# POWER.net
KiCad netlist of a schematic drawn in Altium Designer
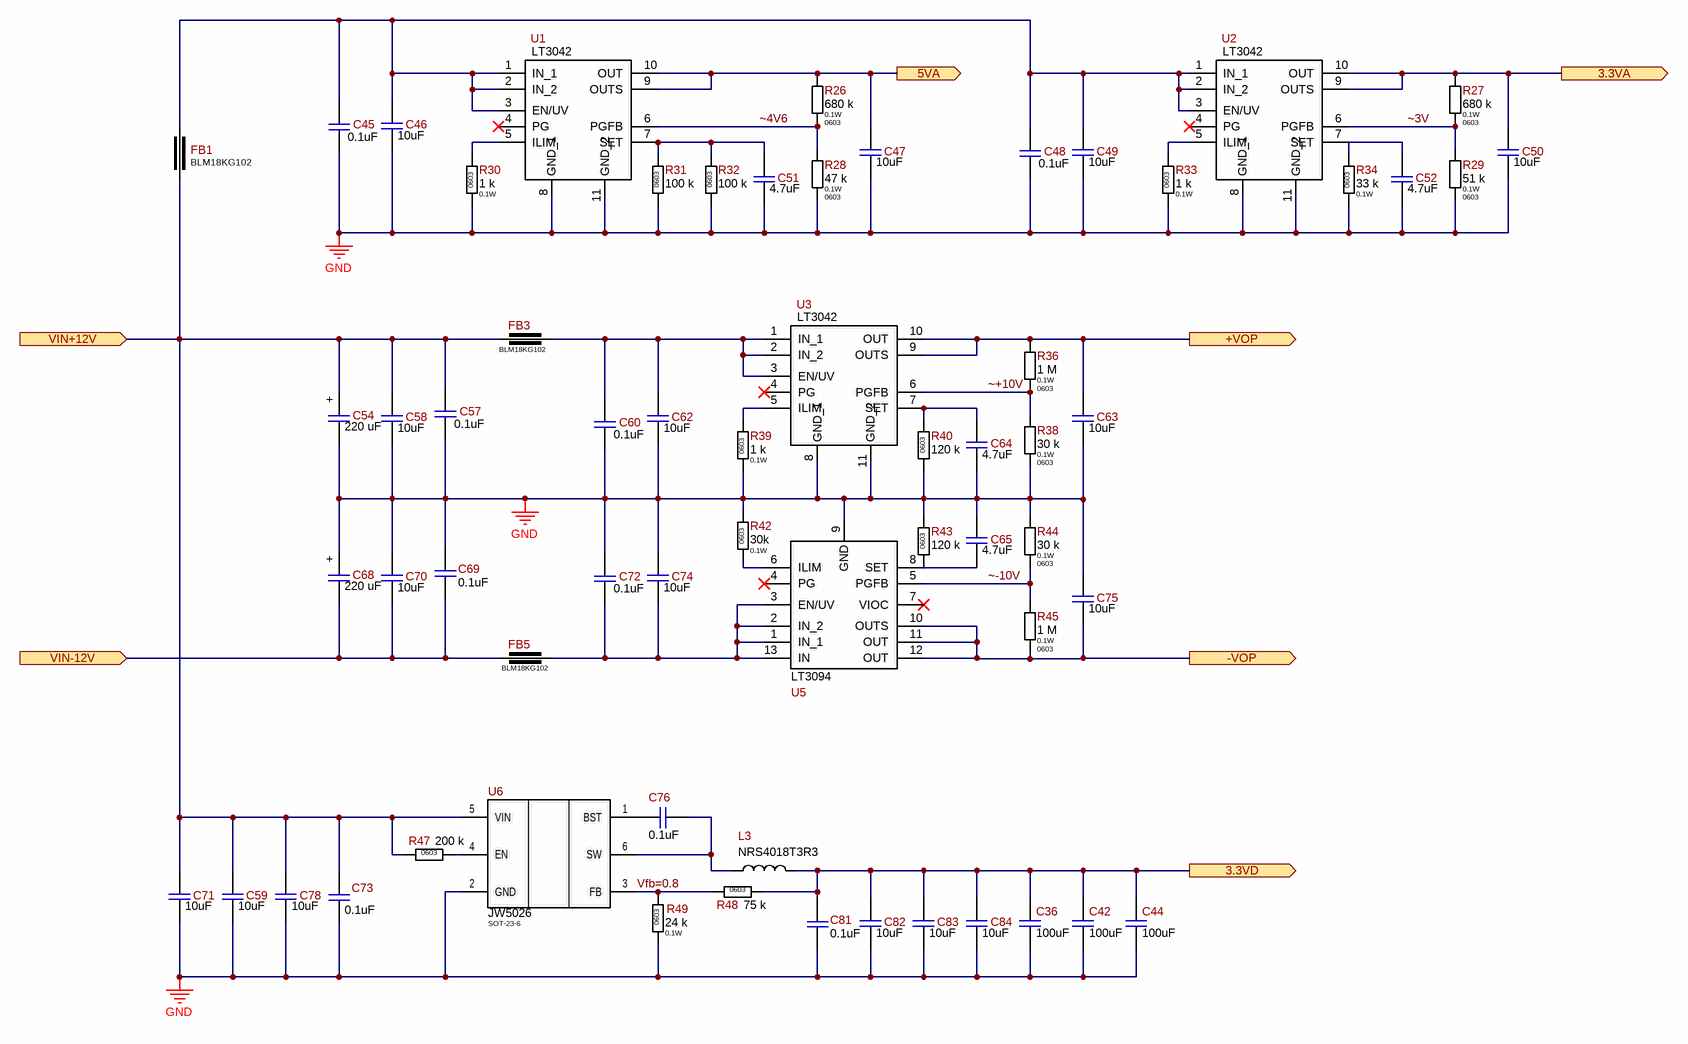
[diagram p0: POWER.SchDoc]

(export (version "E")
  (design (tool "Eeschema 10.0.6"))
  (components
    (comp (ref "C36")
      (value "100uF")
      (footprint "C1206(3216)")
      (description "CAP CER 100UF 10V X5T 1206")
      (fields (field (name "PART NUMBER") "100uF  10V С1206") (field (name "TOLERANCE") "±20%"))
      (libsource (lib "Database") (part "Capacitor_Ceramic"))
    )
    (comp (ref "C42")
      (value "100uF")
      (footprint "C1206(3216)")
      (description "CAP CER 100UF 10V X5T 1206")
      (fields (field (name "PART NUMBER") "100uF  10V С1206") (field (name "TOLERANCE") "±20%"))
      (libsource (lib "Database") (part "Capacitor_Ceramic"))
    )
    (comp (ref "C44")
      (value "100uF")
      (footprint "C1206(3216)")
      (description "CAP CER 100UF 10V X5T 1206")
      (fields (field (name "PART NUMBER") "100uF  10V С1206") (field (name "TOLERANCE") "±20%"))
      (libsource (lib "Database") (part "Capacitor_Ceramic"))
    )
    (comp (ref "C45")
      (value "0.1uF")
      (footprint "C0603(1608)")
      (description "CAP CER 0.1UF 50V X7R 0603")
      (fields (field (name "PART NUMBER") "0.1uF  50V C0603") (field (name "TOLERANCE") "±10%"))
      (libsource (lib "Database") (part "Capacitor_Ceramic"))
    )
    (comp (ref "C46")
      (value "10uF")
      (footprint "C0805(2012)")
      (description "CAP CER 10UF 25V X5R 0805")
      (fields (field (name "PART NUMBER") "10uF  25V C0805") (field (name "TOLERANCE") "±10%"))
      (libsource (lib "Database") (part "Capacitor_Ceramic"))
    )
    (comp (ref "C47")
      (value "10uF")
      (footprint "C0805(2012)")
      (description "CAP CER 10UF 25V X5R 0805")
      (fields (field (name "PART NUMBER") "10uF  25V C0805") (field (name "TOLERANCE") "±10%"))
      (libsource (lib "Database") (part "Capacitor_Ceramic"))
    )
    (comp (ref "C48")
      (value "0.1uF")
      (footprint "C0603(1608)")
      (description "CAP CER 0.1UF 50V X7R 0603")
      (fields (field (name "PART NUMBER") "0.1uF  50V C0603") (field (name "TOLERANCE") "±10%"))
      (libsource (lib "Database") (part "Capacitor_Ceramic"))
    )
    (comp (ref "C49")
      (value "10uF")
      (footprint "C0805(2012)")
      (description "CAP CER 10UF 25V X5R 0805")
      (fields (field (name "PART NUMBER") "10uF  25V C0805") (field (name "TOLERANCE") "±10%"))
      (libsource (lib "Database") (part "Capacitor_Ceramic"))
    )
    (comp (ref "C50")
      (value "10uF")
      (footprint "C0805(2012)")
      (description "CAP CER 10UF 25V X5R 0805")
      (fields (field (name "PART NUMBER") "10uF  25V C0805") (field (name "TOLERANCE") "±10%"))
      (libsource (lib "Database") (part "Capacitor_Ceramic"))
    )
    (comp (ref "C51")
      (value "4.7uF")
      (footprint "C0603(1608)")
      (description "CAP CER 4.7UF 25V X6S 0603")
      (fields (field (name "PART NUMBER") "4.7uF  25V C0603") (field (name "TOLERANCE") "±10%"))
      (libsource (lib "Database") (part "Capacitor_Ceramic"))
    )
    (comp (ref "C52")
      (value "4.7uF")
      (footprint "C0603(1608)")
      (description "CAP CER 4.7UF 25V X6S 0603")
      (fields (field (name "PART NUMBER") "4.7uF  25V C0603") (field (name "TOLERANCE") "±10%"))
      (libsource (lib "Database") (part "Capacitor_Ceramic"))
    )
    (comp (ref "C54")
      (value "220 uF")
      (footprint "CAP 8x9")
      (description "CAP POLY 220 UF 20% 16V 8x9")
      (fields (field (name "PART NUMBER") "220 uF  16V 8 x 9") (field (name "TOLERANCE") "±20%"))
      (libsource (lib "Database") (part "Capacitor_Electrolytic"))
    )
    (comp (ref "C57")
      (value "0.1uF")
      (footprint "C0805(2012)")
      (description "CAP CER 0.1UF 50V X7R 0805")
      (fields (field (name "PART NUMBER") "0.1uF  50V C0805") (field (name "TOLERANCE") "±10%"))
      (libsource (lib "Database") (part "Capacitor_Ceramic"))
    )
    (comp (ref "C58")
      (value "10uF")
      (footprint "C0805(2012)")
      (description "CAP CER 10UF 25V X5R 0805")
      (fields (field (name "PART NUMBER") "10uF  25V C0805") (field (name "TOLERANCE") "±10%"))
      (libsource (lib "Database") (part "Capacitor_Ceramic"))
    )
    (comp (ref "C59")
      (value "10uF")
      (footprint "C0805(2012)")
      (description "CAP CER 10UF 25V X5R 0805")
      (fields (field (name "PART NUMBER") "10uF  25V C0805") (field (name "TOLERANCE") "±10%"))
      (libsource (lib "Database") (part "Capacitor_Ceramic"))
    )
    (comp (ref "C60")
      (value "0.1uF")
      (footprint "C0603(1608)")
      (description "CAP CER 0.1UF 50V X7R 0603")
      (fields (field (name "PART NUMBER") "0.1uF  50V C0603") (field (name "TOLERANCE") "±10%"))
      (libsource (lib "Database") (part "Capacitor_Ceramic"))
    )
    (comp (ref "C62")
      (value "10uF")
      (footprint "C0805(2012)")
      (description "CAP CER 10UF 25V X5R 0805")
      (fields (field (name "PART NUMBER") "10uF  25V C0805") (field (name "TOLERANCE") "±10%"))
      (libsource (lib "Database") (part "Capacitor_Ceramic"))
    )
    (comp (ref "C63")
      (value "10uF")
      (footprint "C0805(2012)")
      (description "CAP CER 10UF 25V X5R 0805")
      (fields (field (name "PART NUMBER") "10uF  25V C0805") (field (name "TOLERANCE") "±10%"))
      (libsource (lib "Database") (part "Capacitor_Ceramic"))
    )
    (comp (ref "C64")
      (value "4.7uF")
      (footprint "C0603(1608)")
      (description "CAP CER 4.7UF 25V X6S 0603")
      (fields (field (name "PART NUMBER") "4.7uF  25V C0603") (field (name "TOLERANCE") "±10%"))
      (libsource (lib "Database") (part "Capacitor_Ceramic"))
    )
    (comp (ref "C65")
      (value "4.7uF")
      (footprint "C0603(1608)")
      (description "CAP CER 4.7UF 25V X6S 0603")
      (fields (field (name "PART NUMBER") "4.7uF  25V C0603") (field (name "TOLERANCE") "±10%"))
      (libsource (lib "Database") (part "Capacitor_Ceramic"))
    )
    (comp (ref "C68")
      (value "220 uF")
      (footprint "CAP 8x9")
      (description "CAP POLY 220 UF 20% 16V 8x9")
      (fields (field (name "PART NUMBER") "220 uF  16V 8 x 9") (field (name "TOLERANCE") "±20%"))
      (libsource (lib "Database") (part "Capacitor_Electrolytic"))
    )
    (comp (ref "C69")
      (value "0.1uF")
      (footprint "C0805(2012)")
      (description "CAP CER 0.1UF 50V X7R 0805")
      (fields (field (name "PART NUMBER") "0.1uF  50V C0805") (field (name "TOLERANCE") "±10%"))
      (libsource (lib "Database") (part "Capacitor_Ceramic"))
    )
    (comp (ref "C70")
      (value "10uF")
      (footprint "C0805(2012)")
      (description "CAP CER 10UF 25V X5R 0805")
      (fields (field (name "PART NUMBER") "10uF  25V C0805") (field (name "TOLERANCE") "±10%"))
      (libsource (lib "Database") (part "Capacitor_Ceramic"))
    )
    (comp (ref "C71")
      (value "10uF")
      (footprint "C0805(2012)")
      (description "CAP CER 10UF 25V X5R 0805")
      (fields (field (name "PART NUMBER") "10uF  25V C0805") (field (name "TOLERANCE") "±10%"))
      (libsource (lib "Database") (part "Capacitor_Ceramic"))
    )
    (comp (ref "C72")
      (value "0.1uF")
      (footprint "C0603(1608)")
      (description "CAP CER 0.1UF 50V X7R 0603")
      (fields (field (name "PART NUMBER") "0.1uF  50V C0603") (field (name "TOLERANCE") "±10%"))
      (libsource (lib "Database") (part "Capacitor_Ceramic"))
    )
    (comp (ref "C73")
      (value "0.1uF")
      (footprint "C0805(2012)")
      (description "CAP CER 0.1UF 50V X7R 0805")
      (fields (field (name "PART NUMBER") "0.1uF  50V C0805") (field (name "TOLERANCE") "±10%"))
      (libsource (lib "Database") (part "Capacitor_Ceramic"))
    )
    (comp (ref "C74")
      (value "10uF")
      (footprint "C0805(2012)")
      (description "CAP CER 10UF 25V X5R 0805")
      (fields (field (name "PART NUMBER") "10uF  25V C0805") (field (name "TOLERANCE") "±10%"))
      (libsource (lib "Database") (part "Capacitor_Ceramic"))
    )
    (comp (ref "C75")
      (value "10uF")
      (footprint "C0805(2012)")
      (description "CAP CER 10UF 25V X5R 0805")
      (fields (field (name "PART NUMBER") "10uF  25V C0805") (field (name "TOLERANCE") "±10%"))
      (libsource (lib "Database") (part "Capacitor_Ceramic"))
    )
    (comp (ref "C76")
      (value "0.1uF")
      (footprint "C0603(1608)")
      (description "CAP CER 0.1UF 50V X7R 0603")
      (fields (field (name "PART NUMBER") "0.1uF  50V C0603") (field (name "TOLERANCE") "±10%"))
      (libsource (lib "Database") (part "Capacitor_Ceramic"))
    )
    (comp (ref "C78")
      (value "10uF")
      (footprint "C0805(2012)")
      (description "CAP CER 10UF 25V X5R 0805")
      (fields (field (name "PART NUMBER") "10uF  25V C0805") (field (name "TOLERANCE") "±10%"))
      (libsource (lib "Database") (part "Capacitor_Ceramic"))
    )
    (comp (ref "C81")
      (value "0.1uF")
      (footprint "C0805(2012)")
      (description "CAP CER 0.1UF 50V X7R 0805")
      (fields (field (name "PART NUMBER") "0.1uF  50V C0805") (field (name "TOLERANCE") "±10%"))
      (libsource (lib "Database") (part "Capacitor_Ceramic"))
    )
    (comp (ref "C82")
      (value "10uF")
      (footprint "C0805(2012)")
      (description "CAP CER 10UF 25V X5R 0805")
      (fields (field (name "PART NUMBER") "10uF  25V C0805") (field (name "TOLERANCE") "±10%"))
      (libsource (lib "Database") (part "Capacitor_Ceramic"))
    )
    (comp (ref "C83")
      (value "10uF")
      (footprint "C0805(2012)")
      (description "CAP CER 10UF 25V X5R 0805")
      (fields (field (name "PART NUMBER") "10uF  25V C0805") (field (name "TOLERANCE") "±10%"))
      (libsource (lib "Database") (part "Capacitor_Ceramic"))
    )
    (comp (ref "C84")
      (value "10uF")
      (footprint "C0805(2012)")
      (description "CAP CER 10UF 25V X5R 0805")
      (fields (field (name "PART NUMBER") "10uF  25V C0805") (field (name "TOLERANCE") "±10%"))
      (libsource (lib "Database") (part "Capacitor_Ceramic"))
    )
    (comp (ref "FB1")
      (value "BLM18KG102")
      (footprint "BLM18(0603)")
      (description "FERRITE BEAD 1 KOHM 0603 1LN")
      (fields
        (field (name "TOLERANCE") "±25%")
        (field (name "MANUFACTURER") "Murata Electronics North America")
      )
      (libsource (lib "") (part "FB_1"))
    )
    (comp (ref "FB3")
      (value "BLM18KG102")
      (footprint "BLM18(0603)")
      (description "FERRITE BEAD 1 KOHM 0603 1LN")
      (fields
        (field (name "TOLERANCE") "±25%")
        (field (name "MANUFACTURER") "Murata Electronics North America")
      )
      (libsource (lib "Database") (part "FB"))
    )
    (comp (ref "FB5")
      (value "BLM18KG102")
      (footprint "BLM18(0603)")
      (description "FERRITE BEAD 1 KOHM 0603 1LN")
      (fields
        (field (name "TOLERANCE") "±25%")
        (field (name "MANUFACTURER") "Murata Electronics North America")
      )
      (libsource (lib "Database") (part "FB"))
    )
    (comp (ref "L3")
      (value "NRS4018T3R3")
      (footprint "WE-LQS SMD 4018")
      (description "FIXED IND 3.3UH 2A 66 MOHM SMD")
      (fields (field (name "TOLERANCE") "±20") (field (name "MANUFACTURER") "TaiyoYuden"))
      (libsource (lib "Database") (part "INDUCTORS"))
    )
    (comp (ref "R26")
      (value "680 k")
      (footprint "R0603")
      (description "RES SMD 680 k OHM  ±1% 1/10W 0603")
      (fields
        (field (name "POWER RATING") "0.1W")
        (field (name "PACKAGE/CASE") "0603")
        (field (name "PART NUMBER") "680 k  R0603")
        (field (name "TOLERANCE") "±1%")
      )
      (libsource (lib "Database") (part "R0603"))
    )
    (comp (ref "R27")
      (value "680 k")
      (footprint "R0603")
      (description "RES SMD 680 k OHM  ±1% 1/10W 0603")
      (fields
        (field (name "POWER RATING") "0.1W")
        (field (name "PACKAGE/CASE") "0603")
        (field (name "PART NUMBER") "680 k  R0603")
        (field (name "TOLERANCE") "±1%")
      )
      (libsource (lib "Database") (part "R0603"))
    )
    (comp (ref "R28")
      (value "47 k")
      (footprint "R0603")
      (description "RES SMD 47 k OHM  ±1% 1/10W 0603")
      (fields
        (field (name "POWER RATING") "0.1W")
        (field (name "PACKAGE/CASE") "0603")
        (field (name "PART NUMBER") "47 k  R0603")
        (field (name "TOLERANCE") "±1%")
      )
      (libsource (lib "Database") (part "R0603"))
    )
    (comp (ref "R29")
      (value "51 k")
      (footprint "R0603")
      (description "RES SMD 51 k OHM  ±1% 1/10W 0603")
      (fields
        (field (name "POWER RATING") "0.1W")
        (field (name "PACKAGE/CASE") "0603")
        (field (name "PART NUMBER") "51 k  R0603")
        (field (name "TOLERANCE") "±1%")
      )
      (libsource (lib "Database") (part "R0603"))
    )
    (comp (ref "R30")
      (value "1 k")
      (footprint "R0603")
      (description "RES SMD 1 k OHM  ±1% 1/10W 0603")
      (fields
        (field (name "POWER RATING") "0.1W")
        (field (name "PACKAGE/CASE") "0603")
        (field (name "PART NUMBER") "1 k  R0603")
        (field (name "TOLERANCE") "±1%")
      )
      (libsource (lib "Database") (part "R0603"))
    )
    (comp (ref "R31")
      (value "100 k")
      (footprint "R0603")
      (description "RES SMD 100 k OHM  ±1% 1/10W 0603")
      (fields
        (field (name "PACKAGE/CASE") "0603")
        (field (name "PART NUMBER") "100 k  R0603")
        (field (name "TOLERANCE") "±1%")
      )
      (libsource (lib "Database") (part "R0603"))
    )
    (comp (ref "R32")
      (value "100 k")
      (footprint "R0603")
      (description "RES SMD 100 k OHM  ±1% 1/10W 0603")
      (fields
        (field (name "PACKAGE/CASE") "0603")
        (field (name "PART NUMBER") "100 k  R0603")
        (field (name "TOLERANCE") "±1%")
      )
      (libsource (lib "Database") (part "R0603"))
    )
    (comp (ref "R33")
      (value "1 k")
      (footprint "R0603")
      (description "RES SMD 1 k OHM  ±1% 1/10W 0603")
      (fields
        (field (name "POWER RATING") "0.1W")
        (field (name "PACKAGE/CASE") "0603")
        (field (name "PART NUMBER") "1 k  R0603")
        (field (name "TOLERANCE") "±1%")
      )
      (libsource (lib "Database") (part "R0603"))
    )
    (comp (ref "R34")
      (value "33 k")
      (footprint "R0603")
      (description "RES SMD 33 k OHM  ±1% 1/10W 0603")
      (fields
        (field (name "POWER RATING") "0.1W")
        (field (name "PACKAGE/CASE") "0603")
        (field (name "PART NUMBER") "33 k  R0603")
        (field (name "TOLERANCE") "±1%")
      )
      (libsource (lib "Database") (part "R0603"))
    )
    (comp (ref "R36")
      (value "1 M")
      (footprint "R0603")
      (description "RES SMD 1 M OHM  ±1% 1/10W 0603")
      (fields
        (field (name "POWER RATING") "0.1W")
        (field (name "PACKAGE/CASE") "0603")
        (field (name "PART NUMBER") "1 M  R0603")
        (field (name "TOLERANCE") "±1%")
      )
      (libsource (lib "Database") (part "R0603"))
    )
    (comp (ref "R38")
      (value "30 k")
      (footprint "R0603")
      (description "RES SMD 30 k OHM  ±1% 1/10W 0603")
      (fields
        (field (name "POWER RATING") "0.1W")
        (field (name "PACKAGE/CASE") "0603")
        (field (name "PART NUMBER") "30 k  R0603")
        (field (name "TOLERANCE") "±1%")
      )
      (libsource (lib "Database") (part "R0603"))
    )
    (comp (ref "R39")
      (value "1 k")
      (footprint "R0603")
      (description "RES SMD 1 k OHM  ±1% 1/10W 0603")
      (fields
        (field (name "POWER RATING") "0.1W")
        (field (name "PACKAGE/CASE") "0603")
        (field (name "PART NUMBER") "1 k  R0603")
        (field (name "TOLERANCE") "±1%")
      )
      (libsource (lib "Database") (part "R0603"))
    )
    (comp (ref "R40")
      (value "120 k")
      (footprint "R0603")
      (description "RES SMD 120 k OHM  ±1% 1/10W 0603")
      (fields
        (field (name "PACKAGE/CASE") "0603")
        (field (name "PART NUMBER") "120 k  R0603")
        (field (name "TOLERANCE") "±1%")
      )
      (libsource (lib "Database") (part "R0603"))
    )
    (comp (ref "R42")
      (value "30k")
      (footprint "R0603")
      (description "RES SMD 120 k OHM  ±1% 1/10W 0603")
      (fields
        (field (name "POWER RATING") "0.1W")
        (field (name "PACKAGE/CASE") "0603")
        (field (name "PART NUMBER") "120 k  R0603")
        (field (name "TOLERANCE") "±1%")
      )
      (libsource (lib "Database") (part "R0603"))
    )
    (comp (ref "R43")
      (value "120 k")
      (footprint "R0603")
      (description "RES SMD 120 k OHM  ±1% 1/10W 0603")
      (fields
        (field (name "PACKAGE/CASE") "0603")
        (field (name "PART NUMBER") "120 k  R0603")
        (field (name "TOLERANCE") "±1%")
      )
      (libsource (lib "Database") (part "R0603"))
    )
    (comp (ref "R44")
      (value "30 k")
      (footprint "R0603")
      (description "RES SMD 30 k OHM  ±1% 1/10W 0603")
      (fields
        (field (name "POWER RATING") "0.1W")
        (field (name "PACKAGE/CASE") "0603")
        (field (name "PART NUMBER") "30 k  R0603")
        (field (name "TOLERANCE") "±1%")
      )
      (libsource (lib "Database") (part "R0603"))
    )
    (comp (ref "R45")
      (value "1 M")
      (footprint "R0603")
      (description "RES SMD 1 M OHM  ±1% 1/10W 0603")
      (fields
        (field (name "POWER RATING") "0.1W")
        (field (name "PACKAGE/CASE") "0603")
        (field (name "PART NUMBER") "1 M  R0603")
        (field (name "TOLERANCE") "±1%")
      )
      (libsource (lib "Database") (part "R0603"))
    )
    (comp (ref "R47")
      (value "200 k")
      (footprint "R0603")
      (description "RES SMD 200 k OHM  ±1% 1/10W 0603")
      (fields
        (field (name "PACKAGE/CASE") "0603")
        (field (name "PART NUMBER") "200 k  R0603")
        (field (name "TOLERANCE") "±1%")
      )
      (libsource (lib "Database") (part "R0603"))
    )
    (comp (ref "R48")
      (value "75 k")
      (footprint "R0603")
      (description "RES SMD 75 k OHM  ±1% 1/10W 0603")
      (fields
        (field (name "PACKAGE/CASE") "0603")
        (field (name "PART NUMBER") "75 k  R0603")
        (field (name "TOLERANCE") "±1%")
      )
      (libsource (lib "Database") (part "R0603"))
    )
    (comp (ref "R49")
      (value "24 k")
      (footprint "R0603")
      (description "RES SMD 24 k OHM  ±1% 1/10W 0603")
      (fields
        (field (name "POWER RATING") "0.1W")
        (field (name "PACKAGE/CASE") "0603")
        (field (name "PART NUMBER") "24 k  R0603")
        (field (name "TOLERANCE") "±1%")
      )
      (libsource (lib "Database") (part "R0603"))
    )
    (comp (ref "U1")
      (value "LT3042")
      (footprint "MSOP-10-EP")
      (fields
        (field (name "MANUFACTURER_PART_NUMBER") "LT3042IMSE#PBF")
        (field (name "MOUSER PART NUMBER") "584-LT3042IMSE#PBF")
      )
      (libsource (lib "Database") (part "LT3042"))
    )
    (comp (ref "U2")
      (value "LT3042")
      (footprint "MSOP-10-EP")
      (fields
        (field (name "MANUFACTURER_PART_NUMBER") "LT3042IMSE#PBF")
        (field (name "MOUSER PART NUMBER") "584-LT3042IMSE#PBF")
      )
      (libsource (lib "Database") (part "LT3042"))
    )
    (comp (ref "U3")
      (value "LT3042")
      (footprint "MSOP-10-EP")
      (fields
        (field (name "MANUFACTURER_PART_NUMBER") "LT3042IMSE#PBF")
        (field (name "MOUSER PART NUMBER") "584-LT3042IMSE#PBF")
      )
      (libsource (lib "Database") (part "LT3042"))
    )
    (comp (ref "U5")
      (value "LT3094")
      (footprint "DFN-12")
      (fields
        (field (name "MANUFACTURER_PART_NUMBER") "LT3042IMSE#PBF")
        (field (name "MOUSER PART NUMBER") "584-LT3042IMSE#PBF")
        (field (name "MANUFACTURER") "Analog Devices Inc.")
      )
      (libsource (lib "Database") (part "LT3094"))
    )
    (comp (ref "U6")
      (value "JW5026")
      (footprint "SOT23-6")
      (fields (field (name "PACKAGE") "SOT-23-6") (field (name "MANUFACTURER") "Joulwatt Technology"))
      (libsource (lib "Database") (part "JW5026"))
    )
  )
  (nets
    (net (code "1") (name "/+VOP") (class "Default")
      (node (ref "C63") (pin "1") (pinfunction "1_1") (pintype "passive"))
      (node (ref "R36") (pin "1") (pinfunction "1_1") (pintype "passive"))
      (node (ref "U3") (pin "10") (pinfunction "OUT_10") (pintype "passive"))
      (node (ref "U3") (pin "9") (pinfunction "OUTS_9") (pintype "passive"))
    )
    (net (code "2") (name "/-VOP") (class "Default")
      (node (ref "C75") (pin "2") (pinfunction "2_2") (pintype "passive"))
      (node (ref "R45") (pin "2") (pinfunction "2_2") (pintype "passive"))
      (node (ref "U5") (pin "10") (pinfunction "OUTS_10") (pintype "passive"))
      (node (ref "U5") (pin "11") (pinfunction "OUT_11") (pintype "passive"))
      (node (ref "U5") (pin "12") (pinfunction "OUT_12") (pintype "passive"))
    )
    (net (code "3") (name "/3.3VA") (class "Default")
      (node (ref "C50") (pin "1") (pinfunction "1_1") (pintype "passive"))
      (node (ref "R27") (pin "2") (pinfunction "2_2") (pintype "passive"))
      (node (ref "U2") (pin "10") (pinfunction "OUT_10") (pintype "passive"))
      (node (ref "U2") (pin "9") (pinfunction "OUTS_9") (pintype "passive"))
    )
    (net (code "4") (name "/3.3VD") (class "Default")
      (node (ref "C36") (pin "1") (pinfunction "1_1") (pintype "passive"))
      (node (ref "C42") (pin "1") (pinfunction "1_1") (pintype "passive"))
      (node (ref "C44") (pin "1") (pinfunction "1_1") (pintype "passive"))
      (node (ref "C81") (pin "2") (pinfunction "2_2") (pintype "passive"))
      (node (ref "C82") (pin "1") (pinfunction "1_1") (pintype "passive"))
      (node (ref "C83") (pin "1") (pinfunction "1_1") (pintype "passive"))
      (node (ref "C84") (pin "1") (pinfunction "1_1") (pintype "passive"))
      (node (ref "L3") (pin "2") (pintype "passive"))
      (node (ref "R48") (pin "2") (pinfunction "2_2") (pintype "passive"))
    )
    (net (code "5") (name "/5VA") (class "Default")
      (node (ref "C47") (pin "1") (pinfunction "1_1") (pintype "passive"))
      (node (ref "R26") (pin "2") (pinfunction "2_2") (pintype "passive"))
      (node (ref "U1") (pin "10") (pinfunction "OUT_10") (pintype "passive"))
      (node (ref "U1") (pin "9") (pinfunction "OUTS_9") (pintype "passive"))
    )
    (net (code "6") (name "/VIN+12V") (class "Default")
      (node (ref "C54") (pin "1") (pinfunction "1_1") (pintype "passive"))
      (node (ref "C57") (pin "2") (pinfunction "2_2") (pintype "passive"))
      (node (ref "C58") (pin "1") (pinfunction "1_1") (pintype "passive"))
      (node (ref "C59") (pin "1") (pinfunction "1_1") (pintype "passive"))
      (node (ref "C71") (pin "1") (pinfunction "1_1") (pintype "passive"))
      (node (ref "C73") (pin "2") (pinfunction "2_2") (pintype "passive"))
      (node (ref "C78") (pin "1") (pinfunction "1_1") (pintype "passive"))
      (node (ref "FB1") (pin "1") (pintype "passive"))
      (node (ref "FB3") (pin "1") (pintype "passive"))
      (node (ref "R47") (pin "1") (pinfunction "1_1") (pintype "passive"))
      (node (ref "U6") (pin "5") (pinfunction "VIN_5") (pintype "passive"))
    )
    (net (code "7") (name "/VIN-12V") (class "Default")
      (node (ref "C68") (pin "2") (pinfunction "2_2") (pintype "passive"))
      (node (ref "C69") (pin "1") (pinfunction "1_1") (pintype "passive"))
      (node (ref "C70") (pin "2") (pinfunction "2_2") (pintype "passive"))
      (node (ref "FB5") (pin "1") (pintype "passive"))
    )
    (net (code "8") (name "/Vfb=0.8") (class "Default")
      (node (ref "R48") (pin "1") (pinfunction "1_1") (pintype "passive"))
      (node (ref "R49") (pin "2") (pinfunction "2_2") (pintype "passive"))
      (node (ref "U6") (pin "3") (pinfunction "FB_3") (pintype "passive"))
    )
    (net (code "9") (name "/~+10V") (class "Default")
      (node (ref "R36") (pin "2") (pinfunction "2_2") (pintype "passive"))
      (node (ref "R38") (pin "1") (pinfunction "1_1") (pintype "passive"))
      (node (ref "U3") (pin "6") (pinfunction "PGFB_6") (pintype "passive"))
    )
    (net (code "10") (name "/~-10V") (class "Default")
      (node (ref "R44") (pin "2") (pinfunction "2_2") (pintype "passive"))
      (node (ref "R45") (pin "1") (pinfunction "1_1") (pintype "passive"))
      (node (ref "U5") (pin "5") (pinfunction "PGFB_5") (pintype "passive"))
    )
    (net (code "11") (name "/~3V") (class "Default")
      (node (ref "R27") (pin "1") (pinfunction "1_1") (pintype "passive"))
      (node (ref "R29") (pin "2") (pinfunction "2_2") (pintype "passive"))
      (node (ref "U2") (pin "6") (pinfunction "PGFB_6") (pintype "passive"))
    )
    (net (code "12") (name "/~4V6") (class "Default")
      (node (ref "R26") (pin "1") (pinfunction "1_1") (pintype "passive"))
      (node (ref "R28") (pin "2") (pinfunction "2_2") (pintype "passive"))
      (node (ref "U1") (pin "6") (pinfunction "PGFB_6") (pintype "passive"))
    )
    (net (code "13") (name "GND") (class "Default")
      (node (ref "C36") (pin "2") (pinfunction "2_2") (pintype "passive"))
      (node (ref "C42") (pin "2") (pinfunction "2_2") (pintype "passive"))
      (node (ref "C44") (pin "2") (pinfunction "2_2") (pintype "passive"))
      (node (ref "C45") (pin "1") (pinfunction "1_1") (pintype "passive"))
      (node (ref "C46") (pin "2") (pinfunction "2_2") (pintype "passive"))
      (node (ref "C47") (pin "2") (pinfunction "2_2") (pintype "passive"))
      (node (ref "C48") (pin "1") (pinfunction "1_1") (pintype "passive"))
      (node (ref "C49") (pin "2") (pinfunction "2_2") (pintype "passive"))
      (node (ref "C50") (pin "2") (pinfunction "2_2") (pintype "passive"))
      (node (ref "C51") (pin "2") (pinfunction "2_2") (pintype "passive"))
      (node (ref "C52") (pin "2") (pinfunction "2_2") (pintype "passive"))
      (node (ref "C54") (pin "2") (pinfunction "2_2") (pintype "passive"))
      (node (ref "C57") (pin "1") (pinfunction "1_1") (pintype "passive"))
      (node (ref "C58") (pin "2") (pinfunction "2_2") (pintype "passive"))
      (node (ref "C59") (pin "2") (pinfunction "2_2") (pintype "passive"))
      (node (ref "C60") (pin "1") (pinfunction "1_1") (pintype "passive"))
      (node (ref "C62") (pin "2") (pinfunction "2_2") (pintype "passive"))
      (node (ref "C63") (pin "2") (pinfunction "2_2") (pintype "passive"))
      (node (ref "C64") (pin "2") (pinfunction "2_2") (pintype "passive"))
      (node (ref "C65") (pin "1") (pinfunction "1_1") (pintype "passive"))
      (node (ref "C68") (pin "1") (pinfunction "1_1") (pintype "passive"))
      (node (ref "C69") (pin "2") (pinfunction "2_2") (pintype "passive"))
      (node (ref "C70") (pin "1") (pinfunction "1_1") (pintype "passive"))
      (node (ref "C71") (pin "2") (pinfunction "2_2") (pintype "passive"))
      (node (ref "C72") (pin "2") (pinfunction "2_2") (pintype "passive"))
      (node (ref "C73") (pin "1") (pinfunction "1_1") (pintype "passive"))
      (node (ref "C74") (pin "1") (pinfunction "1_1") (pintype "passive"))
      (node (ref "C75") (pin "1") (pinfunction "1_1") (pintype "passive"))
      (node (ref "C78") (pin "2") (pinfunction "2_2") (pintype "passive"))
      (node (ref "C81") (pin "1") (pinfunction "1_1") (pintype "passive"))
      (node (ref "C82") (pin "2") (pinfunction "2_2") (pintype "passive"))
      (node (ref "C83") (pin "2") (pinfunction "2_2") (pintype "passive"))
      (node (ref "C84") (pin "2") (pinfunction "2_2") (pintype "passive"))
      (node (ref "R28") (pin "1") (pinfunction "1_1") (pintype "passive"))
      (node (ref "R29") (pin "1") (pinfunction "1_1") (pintype "passive"))
      (node (ref "R30") (pin "1") (pinfunction "1_1") (pintype "passive"))
      (node (ref "R31") (pin "1") (pinfunction "1_1") (pintype "passive"))
      (node (ref "R32") (pin "1") (pinfunction "1_1") (pintype "passive"))
      (node (ref "R33") (pin "1") (pinfunction "1_1") (pintype "passive"))
      (node (ref "R34") (pin "1") (pinfunction "1_1") (pintype "passive"))
      (node (ref "R38") (pin "2") (pinfunction "2_2") (pintype "passive"))
      (node (ref "R39") (pin "1") (pinfunction "1_1") (pintype "passive"))
      (node (ref "R40") (pin "1") (pinfunction "1_1") (pintype "passive"))
      (node (ref "R42") (pin "2") (pinfunction "2_2") (pintype "passive"))
      (node (ref "R43") (pin "2") (pinfunction "2_2") (pintype "passive"))
      (node (ref "R44") (pin "1") (pinfunction "1_1") (pintype "passive"))
      (node (ref "R49") (pin "1") (pinfunction "1_1") (pintype "passive"))
      (node (ref "U1") (pin "11") (pinfunction "GND_2_11") (pintype "passive"))
      (node (ref "U1") (pin "8") (pinfunction "GND_1_8") (pintype "passive"))
      (node (ref "U2") (pin "11") (pinfunction "GND_2_11") (pintype "passive"))
      (node (ref "U2") (pin "8") (pinfunction "GND_1_8") (pintype "passive"))
      (node (ref "U3") (pin "11") (pinfunction "GND_2_11") (pintype "passive"))
      (node (ref "U3") (pin "8") (pinfunction "GND_1_8") (pintype "passive"))
      (node (ref "U5") (pin "9") (pinfunction "GND_9") (pintype "passive"))
      (node (ref "U6") (pin "2") (pinfunction "GND_2") (pintype "passive"))
    )
    (net (code "14") (name "Net-(U1-EN{slash}UV)") (class "Default")
      (node (ref "C45") (pin "2") (pinfunction "2_2") (pintype "passive"))
      (node (ref "C46") (pin "1") (pinfunction "1_1") (pintype "passive"))
      (node (ref "C48") (pin "2") (pinfunction "2_2") (pintype "passive"))
      (node (ref "C49") (pin "1") (pinfunction "1_1") (pintype "passive"))
      (node (ref "FB1") (pin "2") (pintype "passive"))
      (node (ref "U1") (pin "1") (pinfunction "IN_1_1") (pintype "passive"))
      (node (ref "U1") (pin "2") (pinfunction "IN_2_2") (pintype "passive"))
      (node (ref "U1") (pin "3") (pinfunction "EN/UV_3") (pintype "passive"))
      (node (ref "U2") (pin "1") (pinfunction "IN_1_1") (pintype "passive"))
      (node (ref "U2") (pin "2") (pinfunction "IN_2_2") (pintype "passive"))
      (node (ref "U2") (pin "3") (pinfunction "EN/UV_3") (pintype "passive"))
    )
    (net (code "15") (name "Net-(U1-ILIM)") (class "Default")
      (node (ref "R30") (pin "2") (pinfunction "2_2") (pintype "passive"))
      (node (ref "U1") (pin "5") (pinfunction "ILIM_5") (pintype "passive"))
    )
    (net (code "16") (name "Net-(U1-SET)") (class "Default")
      (node (ref "C51") (pin "1") (pinfunction "1_1") (pintype "passive"))
      (node (ref "R31") (pin "2") (pinfunction "2_2") (pintype "passive"))
      (node (ref "R32") (pin "2") (pinfunction "2_2") (pintype "passive"))
      (node (ref "U1") (pin "7") (pinfunction "SET_7") (pintype "passive"))
    )
    (net (code "17") (name "Net-(U2-ILIM)") (class "Default")
      (node (ref "R33") (pin "2") (pinfunction "2_2") (pintype "passive"))
      (node (ref "U2") (pin "5") (pinfunction "ILIM_5") (pintype "passive"))
    )
    (net (code "18") (name "Net-(U2-SET)") (class "Default")
      (node (ref "C52") (pin "1") (pinfunction "1_1") (pintype "passive"))
      (node (ref "R34") (pin "2") (pinfunction "2_2") (pintype "passive"))
      (node (ref "U2") (pin "7") (pinfunction "SET_7") (pintype "passive"))
    )
    (net (code "19") (name "Net-(U3-EN{slash}UV)") (class "Default")
      (node (ref "C60") (pin "2") (pinfunction "2_2") (pintype "passive"))
      (node (ref "C62") (pin "1") (pinfunction "1_1") (pintype "passive"))
      (node (ref "FB3") (pin "2") (pintype "passive"))
      (node (ref "U3") (pin "1") (pinfunction "IN_1_1") (pintype "passive"))
      (node (ref "U3") (pin "2") (pinfunction "IN_2_2") (pintype "passive"))
      (node (ref "U3") (pin "3") (pinfunction "EN/UV_3") (pintype "passive"))
    )
    (net (code "20") (name "Net-(U3-ILIM)") (class "Default")
      (node (ref "R39") (pin "2") (pinfunction "2_2") (pintype "passive"))
      (node (ref "U3") (pin "5") (pinfunction "ILIM_5") (pintype "passive"))
    )
    (net (code "21") (name "Net-(U3-SET)") (class "Default")
      (node (ref "C64") (pin "1") (pinfunction "1_1") (pintype "passive"))
      (node (ref "R40") (pin "2") (pinfunction "2_2") (pintype "passive"))
      (node (ref "U3") (pin "7") (pinfunction "SET_7") (pintype "passive"))
    )
    (net (code "22") (name "Net-(U5-EN{slash}UV)") (class "Default")
      (node (ref "C72") (pin "1") (pinfunction "1_1") (pintype "passive"))
      (node (ref "C74") (pin "2") (pinfunction "2_2") (pintype "passive"))
      (node (ref "FB5") (pin "2") (pintype "passive"))
      (node (ref "U5") (pin "1") (pinfunction "IN_1_1") (pintype "passive"))
      (node (ref "U5") (pin "13") (pinfunction "IN_13") (pintype "passive"))
      (node (ref "U5") (pin "2") (pinfunction "IN_2_2") (pintype "passive"))
      (node (ref "U5") (pin "3") (pinfunction "EN/UV_3") (pintype "passive"))
    )
    (net (code "23") (name "Net-(U5-ILIM)") (class "Default")
      (node (ref "R42") (pin "1") (pinfunction "1_1") (pintype "passive"))
      (node (ref "U5") (pin "6") (pinfunction "ILIM_6") (pintype "passive"))
    )
    (net (code "24") (name "Net-(U5-SET)") (class "Default")
      (node (ref "C65") (pin "2") (pinfunction "2_2") (pintype "passive"))
      (node (ref "R43") (pin "1") (pinfunction "1_1") (pintype "passive"))
      (node (ref "U5") (pin "8") (pinfunction "SET_8") (pintype "passive"))
    )
    (net (code "25") (name "Net-(U6-BST)") (class "Default")
      (node (ref "C76") (pin "1") (pinfunction "1_1") (pintype "passive"))
      (node (ref "U6") (pin "1") (pinfunction "BST_1") (pintype "passive"))
    )
    (net (code "26") (name "Net-(U6-EN)") (class "Default")
      (node (ref "R47") (pin "2") (pinfunction "2_2") (pintype "passive"))
      (node (ref "U6") (pin "4") (pinfunction "EN_4") (pintype "passive"))
    )
    (net (code "27") (name "Net-(U6-SW)") (class "Default")
      (node (ref "C76") (pin "2") (pinfunction "2_2") (pintype "passive"))
      (node (ref "L3") (pin "1") (pintype "passive"))
      (node (ref "U6") (pin "6") (pinfunction "SW_6") (pintype "passive"))
    )
    (net (code "28") (name "unconnected-(U1-PG-Pad4)") (class "Default")
      (node (ref "U1") (pin "4") (pinfunction "PG_4") (pintype "passive+no_connect"))
    )
    (net (code "29") (name "unconnected-(U2-PG-Pad4)") (class "Default")
      (node (ref "U2") (pin "4") (pinfunction "PG_4") (pintype "passive+no_connect"))
    )
    (net (code "30") (name "unconnected-(U3-PG-Pad4)") (class "Default")
      (node (ref "U3") (pin "4") (pinfunction "PG_4") (pintype "passive+no_connect"))
    )
    (net (code "31") (name "unconnected-(U5-PG-Pad4)") (class "Default")
      (node (ref "U5") (pin "4") (pinfunction "PG_4") (pintype "passive+no_connect"))
    )
    (net (code "32") (name "unconnected-(U5-VIOC-Pad7)") (class "Default")
      (node (ref "U5") (pin "7") (pinfunction "VIOC_7") (pintype "passive+no_connect"))
    )
  )
)
